# ADS1248Shield.net
KiCad netlist of a schematic drawn in EAGLE
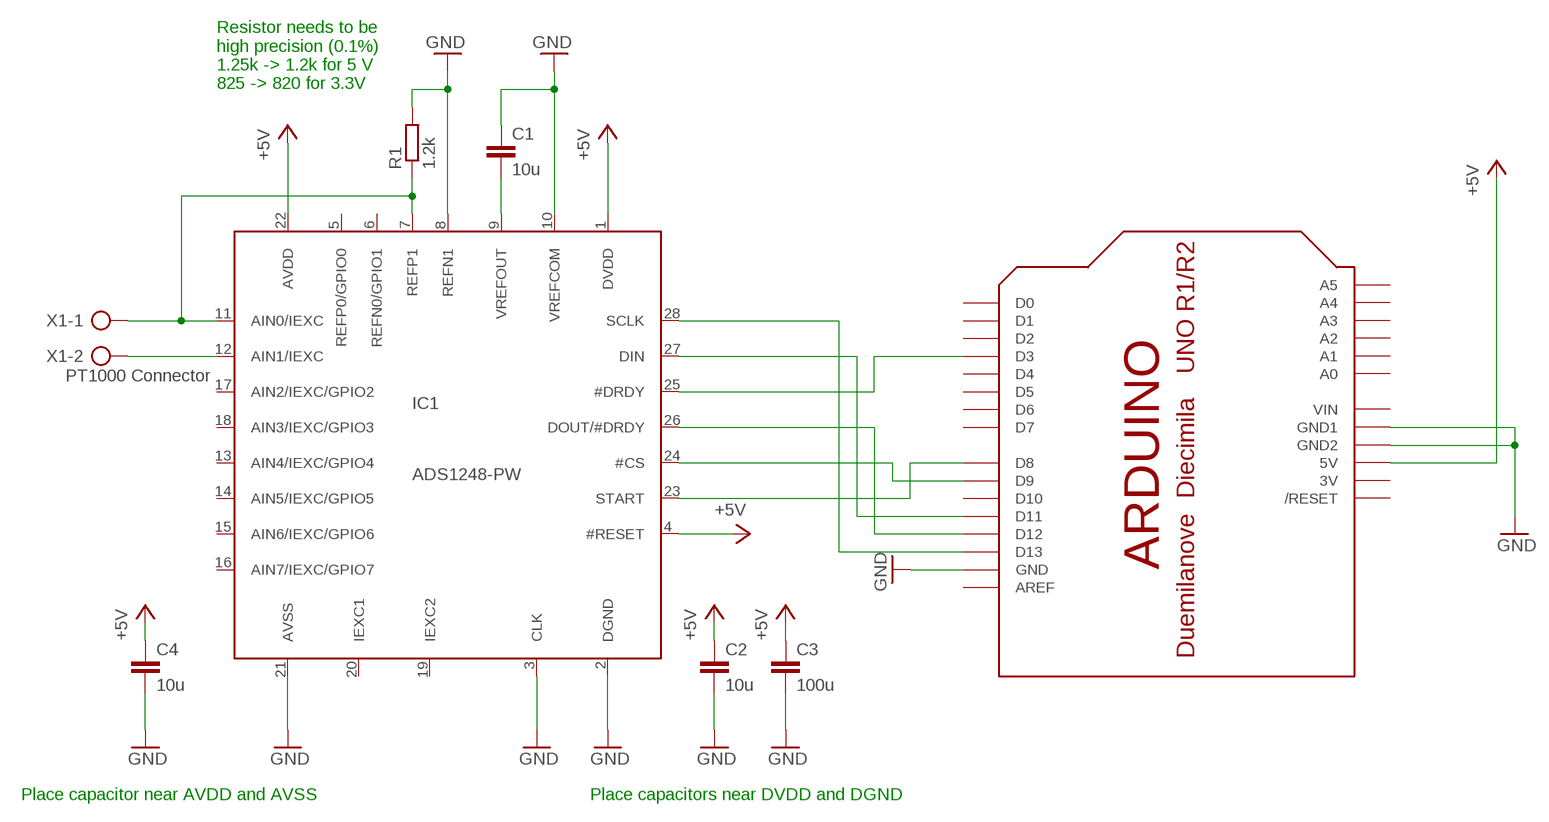
[diagram p0: schematic, sheet 1]

(export (version "E")
  (design (tool "Eeschema 10.0.6"))
  (components
    (comp (ref "C1")
      (value "10u")
      (footprint "eagle-import:C2.5-4")
      (libsource (lib "eagle-import") (part "C2.5/4"))
    )
    (comp (ref "C2")
      (value "10u")
      (footprint "eagle-import:C2.5-4")
      (libsource (lib "eagle-import") (part "C2.5/4"))
    )
    (comp (ref "C3")
      (value "100u")
      (footprint "eagle-import:C2.5-4")
      (libsource (lib "eagle-import") (part "C2.5/4"))
    )
    (comp (ref "C4")
      (value "10u")
      (footprint "eagle-import:C2.5-4")
      (libsource (lib "eagle-import") (part "C2.5/4"))
    )
    (comp (ref "IC1")
      (value "ADS1248-PW")
      (footprint "eagle-import:TSSOP28")
      (libsource (lib "eagle-import") (part "ADS1248-PW"))
    )
    (comp (ref "R1")
      (value "1.2k")
      (footprint "eagle-import:0204V")
      (libsource (lib "eagle-import") (part "R-EU_0204/2V"))
    )
    (comp (ref "U$1")
      (value "ARDUINOUNO")
      (footprint "eagle-import:ARDUINO")
      (libsource (lib "eagle-import") (part "ARDUINOUNO"))
    )
    (comp (ref "X1")
      (value "PT1000 Connector")
      (footprint "eagle-import:AK300_2")
      (libsource (lib "eagle-import") (part "AK300/2"))
    )
  )
  (nets
    (net (code "1") (name "+5V") (class "Default")
      (node (ref "C2") (pin "1") (pinfunction "1_1") (pintype "passive"))
      (node (ref "C3") (pin "1") (pinfunction "1_1") (pintype "passive"))
      (node (ref "C4") (pin "1") (pinfunction "1_1") (pintype "passive"))
      (node (ref "IC1") (pin "1") (pinfunction "DVDD_1") (pintype "bidirectional"))
      (node (ref "IC1") (pin "22") (pinfunction "AVDD_22") (pintype "bidirectional"))
      (node (ref "IC1") (pin "4") (pinfunction "#RESET_4") (pintype "bidirectional"))
      (node (ref "U$1") (pin "5V") (pinfunction "5V_5V") (pintype "power_in"))
    )
    (net (code "2") (name "/3V") (class "Default")
      (node (ref "U$1") (pin "3V") (pinfunction "3V_3V") (pintype "power_in"))
    )
    (net (code "3") (name "/VIN") (class "Default")
      (node (ref "U$1") (pin "VIN") (pinfunction "VIN_VIN") (pintype "power_in"))
    )
    (net (code "4") (name "GND") (class "Default")
      (node (ref "C1") (pin "1") (pinfunction "1_1") (pintype "passive"))
      (node (ref "C2") (pin "2") (pinfunction "2_2") (pintype "passive"))
      (node (ref "C3") (pin "2") (pinfunction "2_2") (pintype "passive"))
      (node (ref "C4") (pin "2") (pinfunction "2_2") (pintype "passive"))
      (node (ref "IC1") (pin "10") (pinfunction "VREFCOM_10") (pintype "bidirectional"))
      (node (ref "IC1") (pin "2") (pinfunction "DGND_2") (pintype "bidirectional"))
      (node (ref "IC1") (pin "21") (pinfunction "AVSS_21") (pintype "bidirectional"))
      (node (ref "IC1") (pin "3") (pinfunction "CLK_3") (pintype "bidirectional"))
      (node (ref "IC1") (pin "8") (pinfunction "REFN1_8") (pintype "bidirectional"))
      (node (ref "R1") (pin "2") (pinfunction "2_2") (pintype "passive"))
      (node (ref "U$1") (pin "GND") (pinfunction "GND_GND") (pintype "power_in"))
      (node (ref "U$1") (pin "GND1") (pinfunction "GND1_GND1") (pintype "power_in"))
      (node (ref "U$1") (pin "GND2") (pinfunction "GND2_GND2") (pintype "power_in"))
    )
    (net (code "5") (name "Net-(IC1-#CS)") (class "Default")
      (node (ref "IC1") (pin "24") (pinfunction "#CS_24") (pintype "bidirectional"))
      (node (ref "U$1") (pin "D9") (pinfunction "D9_D9") (pintype "bidirectional"))
    )
    (net (code "6") (name "Net-(IC1-#DRDY)") (class "Default")
      (node (ref "IC1") (pin "25") (pinfunction "#DRDY_25") (pintype "bidirectional"))
      (node (ref "U$1") (pin "D3") (pinfunction "D3_D3") (pintype "bidirectional"))
    )
    (net (code "7") (name "Net-(IC1-AIN0{slash}IEXC)") (class "Default")
      (node (ref "IC1") (pin "11") (pinfunction "AIN0/IEXC_11") (pintype "bidirectional"))
      (node (ref "IC1") (pin "7") (pinfunction "REFP1_7") (pintype "bidirectional"))
      (node (ref "R1") (pin "1") (pinfunction "1_1") (pintype "passive"))
      (node (ref "X1") (pin "1") (pinfunction "KL_1") (pintype "passive"))
    )
    (net (code "8") (name "Net-(IC1-AIN1{slash}IEXC)") (class "Default")
      (node (ref "IC1") (pin "12") (pinfunction "AIN1/IEXC_12") (pintype "bidirectional"))
      (node (ref "X1") (pin "2") (pinfunction "KL_2") (pintype "passive"))
    )
    (net (code "9") (name "Net-(IC1-DIN)") (class "Default")
      (node (ref "IC1") (pin "27") (pinfunction "DIN_27") (pintype "bidirectional"))
      (node (ref "U$1") (pin "D11") (pinfunction "D11_D11") (pintype "bidirectional"))
    )
    (net (code "10") (name "Net-(IC1-DOUT{slash}#DRDY)") (class "Default")
      (node (ref "IC1") (pin "26") (pinfunction "DOUT/#DRDY_26") (pintype "bidirectional"))
      (node (ref "U$1") (pin "D12") (pinfunction "D12_D12") (pintype "bidirectional"))
    )
    (net (code "11") (name "Net-(IC1-SCLK)") (class "Default")
      (node (ref "IC1") (pin "28") (pinfunction "SCLK_28") (pintype "bidirectional"))
      (node (ref "U$1") (pin "D13") (pinfunction "D13_D13") (pintype "bidirectional"))
    )
    (net (code "12") (name "Net-(IC1-START)") (class "Default")
      (node (ref "IC1") (pin "23") (pinfunction "START_23") (pintype "bidirectional"))
      (node (ref "U$1") (pin "D8") (pinfunction "D8_D8") (pintype "bidirectional"))
    )
    (net (code "13") (name "Net-(IC1-VREFOUT)") (class "Default")
      (node (ref "C1") (pin "2") (pinfunction "2_2") (pintype "passive"))
      (node (ref "IC1") (pin "9") (pinfunction "VREFOUT_9") (pintype "bidirectional"))
    )
    (net (code "14") (name "unconnected-(IC1-AIN2{slash}IEXC{slash}GPIO2-Pad17)") (class "Default")
      (node (ref "IC1") (pin "17") (pinfunction "AIN2/IEXC/GPIO2_17") (pintype "bidirectional"))
    )
    (net (code "15") (name "unconnected-(IC1-AIN3{slash}IEXC{slash}GPIO3-Pad18)") (class "Default")
      (node (ref "IC1") (pin "18") (pinfunction "AIN3/IEXC/GPIO3_18") (pintype "bidirectional"))
    )
    (net (code "16") (name "unconnected-(IC1-AIN4{slash}IEXC{slash}GPIO4-Pad13)") (class "Default")
      (node (ref "IC1") (pin "13") (pinfunction "AIN4/IEXC/GPIO4_13") (pintype "bidirectional"))
    )
    (net (code "17") (name "unconnected-(IC1-AIN5{slash}IEXC{slash}GPIO5-Pad14)") (class "Default")
      (node (ref "IC1") (pin "14") (pinfunction "AIN5/IEXC/GPIO5_14") (pintype "bidirectional"))
    )
    (net (code "18") (name "unconnected-(IC1-AIN6{slash}IEXC{slash}GPIO6-Pad15)") (class "Default")
      (node (ref "IC1") (pin "15") (pinfunction "AIN6/IEXC/GPIO6_15") (pintype "bidirectional"))
    )
    (net (code "19") (name "unconnected-(IC1-AIN7{slash}IEXC{slash}GPIO7-Pad16)") (class "Default")
      (node (ref "IC1") (pin "16") (pinfunction "AIN7/IEXC/GPIO7_16") (pintype "bidirectional"))
    )
    (net (code "20") (name "unconnected-(IC1-IEXC1-Pad20)") (class "Default")
      (node (ref "IC1") (pin "20") (pinfunction "IEXC1_20") (pintype "bidirectional"))
    )
    (net (code "21") (name "unconnected-(IC1-IEXC2-Pad19)") (class "Default")
      (node (ref "IC1") (pin "19") (pinfunction "IEXC2_19") (pintype "bidirectional"))
    )
    (net (code "22") (name "unconnected-(IC1-REFN0{slash}GPIO1-Pad6)") (class "Default")
      (node (ref "IC1") (pin "6") (pinfunction "REFN0/GPIO1_6") (pintype "bidirectional"))
    )
    (net (code "23") (name "unconnected-(IC1-REFP0{slash}GPIO0-Pad5)") (class "Default")
      (node (ref "IC1") (pin "5") (pinfunction "REFP0/GPIO0_5") (pintype "bidirectional"))
    )
    (net (code "24") (name "unconnected-(U$1-PadA0)") (class "Default")
      (node (ref "U$1") (pin "A0") (pinfunction "A0_A0") (pintype "bidirectional"))
    )
    (net (code "25") (name "unconnected-(U$1-PadA1)") (class "Default")
      (node (ref "U$1") (pin "A1") (pinfunction "A1_A1") (pintype "bidirectional"))
    )
    (net (code "26") (name "unconnected-(U$1-PadA2)") (class "Default")
      (node (ref "U$1") (pin "A2") (pinfunction "A2_A2") (pintype "bidirectional"))
    )
    (net (code "27") (name "unconnected-(U$1-PadA3)") (class "Default")
      (node (ref "U$1") (pin "A3") (pinfunction "A3_A3") (pintype "bidirectional"))
    )
    (net (code "28") (name "unconnected-(U$1-PadA4)") (class "Default")
      (node (ref "U$1") (pin "A4") (pinfunction "A4_A4") (pintype "bidirectional"))
    )
    (net (code "29") (name "unconnected-(U$1-PadA5)") (class "Default")
      (node (ref "U$1") (pin "A5") (pinfunction "A5_A5") (pintype "bidirectional"))
    )
    (net (code "30") (name "unconnected-(U$1-PadAREF)") (class "Default")
      (node (ref "U$1") (pin "AREF") (pinfunction "AREF_AREF") (pintype "bidirectional"))
    )
    (net (code "31") (name "unconnected-(U$1-PadD0)") (class "Default")
      (node (ref "U$1") (pin "D0") (pinfunction "D0_D0") (pintype "bidirectional"))
    )
    (net (code "32") (name "unconnected-(U$1-PadD1)") (class "Default")
      (node (ref "U$1") (pin "D1") (pinfunction "D1_D1") (pintype "bidirectional"))
    )
    (net (code "33") (name "unconnected-(U$1-PadD2)") (class "Default")
      (node (ref "U$1") (pin "D2") (pinfunction "D2_D2") (pintype "bidirectional"))
    )
    (net (code "34") (name "unconnected-(U$1-PadD4)") (class "Default")
      (node (ref "U$1") (pin "D4") (pinfunction "D4_D4") (pintype "bidirectional"))
    )
    (net (code "35") (name "unconnected-(U$1-PadD5)") (class "Default")
      (node (ref "U$1") (pin "D5") (pinfunction "D5_D5") (pintype "bidirectional"))
    )
    (net (code "36") (name "unconnected-(U$1-PadD6)") (class "Default")
      (node (ref "U$1") (pin "D6") (pinfunction "D6_D6") (pintype "bidirectional"))
    )
    (net (code "37") (name "unconnected-(U$1-PadD7)") (class "Default")
      (node (ref "U$1") (pin "D7") (pinfunction "D7_D7") (pintype "bidirectional"))
    )
    (net (code "38") (name "unconnected-(U$1-PadD10)") (class "Default")
      (node (ref "U$1") (pin "D10") (pinfunction "D10_D10") (pintype "bidirectional"))
    )
    (net (code "39") (name "unconnected-(U$1-{slash}RESET-PadRESET)") (class "Default")
      (node (ref "U$1") (pin "RESET") (pinfunction "/RESET_RESET") (pintype "bidirectional"))
    )
  )
)
